# Sheet2.net
KiCad netlist of a schematic drawn in Altium Designer
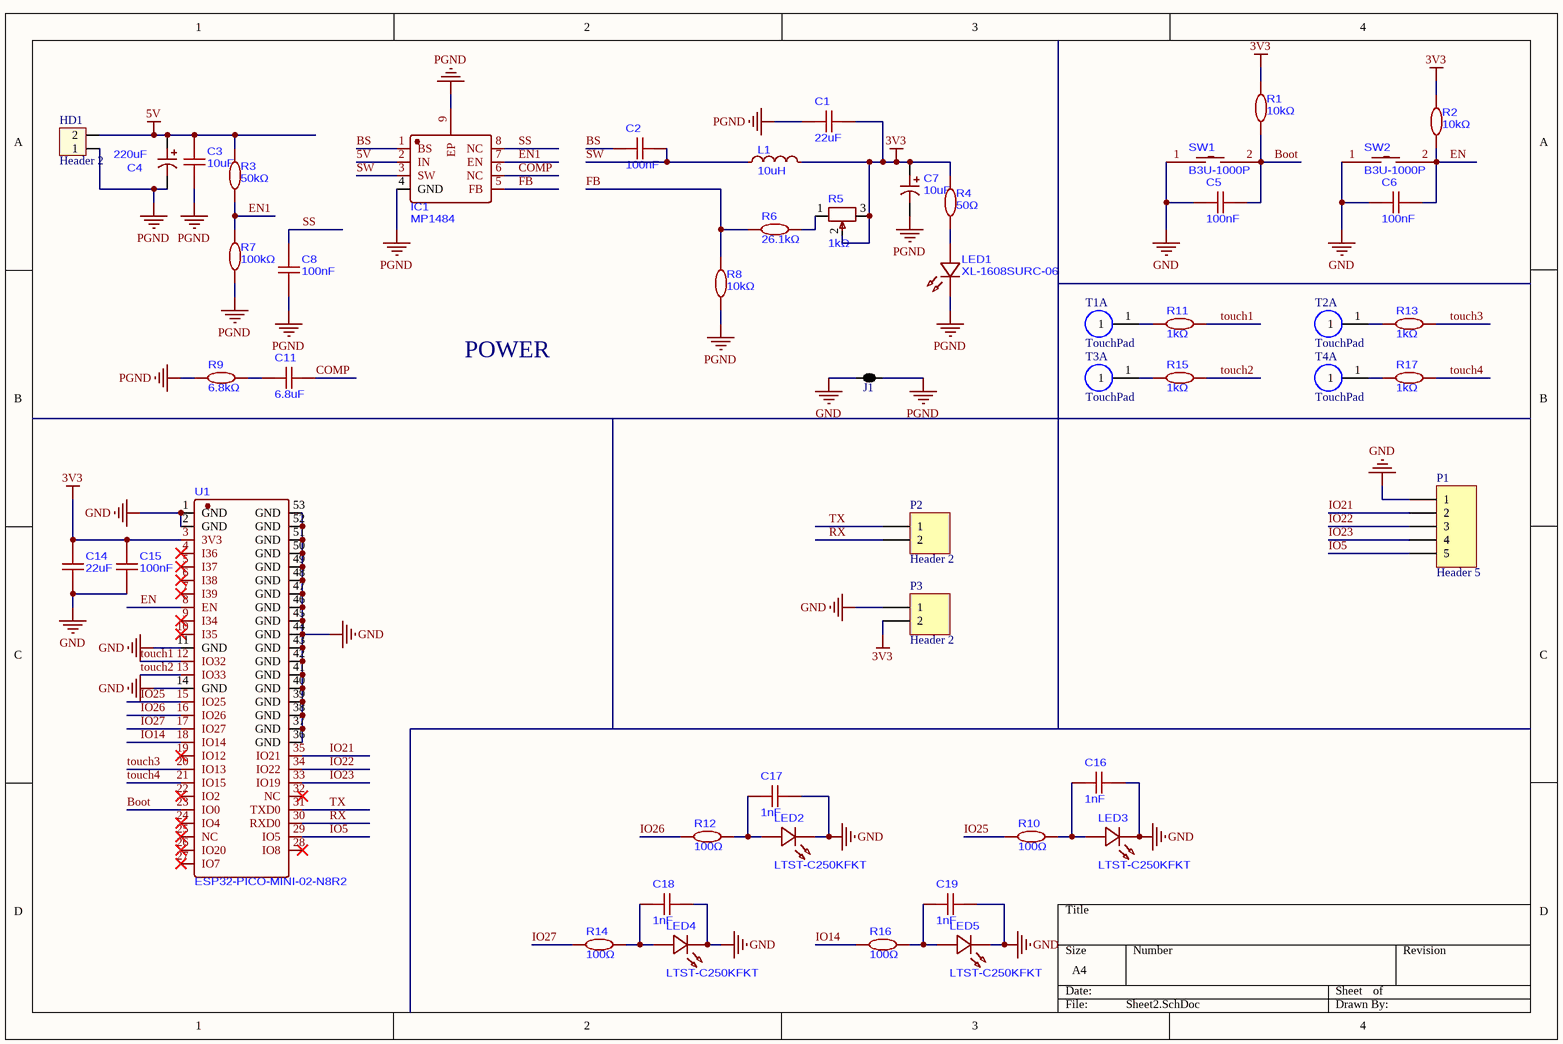
[diagram p0: Sheet2.SchDoc]

(export (version "E")
  (design (tool "Eeschema 10.0.6"))
  (components
    (comp (ref "C1")
      (value "22uF")
      (footprint "C0603")
      (description "10V 22uF X5R ±20% 0603 Ceramic Capacitors ROHS")
      (libsource (lib "Schlib2") (part "CL10A226MP8NUNE"))
    )
    (comp (ref "C2")
      (value "100nF")
      (footprint "C0603")
      (description "50V 100nF X7R ±10% 0603 Ceramic Capacitors ROHS")
      (libsource (lib "Schlib2") (part "CC0603KRX7R9BB104"))
    )
    (comp (ref "C3")
      (value "10uF")
      (footprint "C0603")
      (description "10V 10uF X5R ±10% 0603 Ceramic Capacitors ROHS")
      (libsource (lib "Schlib2") (part "CL10A106KP8NNNC"))
    )
    (comp (ref "C4")
      (value "220uF")
      (footprint "CAP-SMD_BD6.3-L6.6-W6.6-FD")
      (description "220uF 10V ±20% 69mA@120Hz SMD,D6.3xL5.4mm Aluminum Electrolytic Capacitors ROHS")
      (libsource (lib "Schlib2") (part "RVT220UF10V67RV0037"))
    )
    (comp (ref "C5")
      (value "100nF")
      (footprint "C0603")
      (description "50V 100nF X7R ±10% 0603 Ceramic Capacitors ROHS")
      (libsource (lib "Schlib2") (part "CC0603KRX7R9BB104"))
    )
    (comp (ref "C6")
      (value "100nF")
      (footprint "C0603")
      (description "50V 100nF X7R ±10% 0603 Ceramic Capacitors ROHS")
      (libsource (lib "Schlib2") (part "CC0603KRX7R9BB104"))
    )
    (comp (ref "C7")
      (value "10uF")
      (footprint "CAP-SMD_BD6.3-L6.6-W6.6-FD")
      (description "10uF 50V 24mA@120Hz ±20% SMD,D5xL5.4mm Aluminum Electrolytic Capacitors ROHS")
      (libsource (lib "Schlib2") (part "RST10UF50V016"))
    )
    (comp (ref "C8")
      (value "100nF")
      (footprint "C0603")
      (description "50V 100nF X7R ±10% 0603 Ceramic Capacitors ROHS")
      (libsource (lib "Schlib2") (part "CC0603KRX7R9BB104"))
    )
    (comp (ref "C11")
      (value "6.8uF")
      (footprint "C0603")
      (description "10V 6.8uF X5R ±10% 0603 Ceramic Capacitors ROHS")
      (libsource (lib "Schlib2") (part "C1608X5R1A685KT000E"))
    )
    (comp (ref "C14")
      (value "22uF")
      (footprint "C0603")
      (description "10V 22uF X5R ±20% 0603 Ceramic Capacitors ROHS")
      (libsource (lib "Schlib2") (part "CL10A226MP8NUNE"))
    )
    (comp (ref "C15")
      (value "100nF")
      (footprint "C0603")
      (description "50V 100nF X7R ±10% 0603 Ceramic Capacitors ROHS")
      (libsource (lib "Schlib2") (part "CC0603KRX7R9BB104"))
    )
    (comp (ref "C16")
      (value "1nF")
      (footprint "C0603")
      (description "50V 1nF X7R ±10% 0603 Ceramic Capacitors ROHS")
      (libsource (lib "Schlib2") (part "CL10B102KB8NNNC"))
    )
    (comp (ref "C17")
      (value "1nF")
      (footprint "C0603")
      (description "50V 1nF X7R ±10% 0603 Ceramic Capacitors ROHS")
      (libsource (lib "Schlib2") (part "CL10B102KB8NNNC"))
    )
    (comp (ref "C18")
      (value "1nF")
      (footprint "C0603")
      (description "50V 1nF X7R ±10% 0603 Ceramic Capacitors ROHS")
      (libsource (lib "Schlib2") (part "CL10B102KB8NNNC"))
    )
    (comp (ref "C19")
      (value "1nF")
      (footprint "C0603")
      (description "50V 1nF X7R ±10% 0603 Ceramic Capacitors ROHS")
      (libsource (lib "Schlib2") (part "CL10B102KB8NNNC"))
    )
    (comp (ref "HD1")
      (value "Header 2")
      (footprint "HED2")
      (description "Header 2 (Green)")
      (libsource (lib "Library AL") (part "Hed2"))
    )
    (comp (ref "IC1")
      (value "MP1484")
      (footprint "SOP-8_L4.9-W3.9-P1.27-LS6.0-BL-EP3.1")
      (description "The MP1484 is a monolithic synchronous buck \r\nregulator.")
      (libsource (lib "Schlib2") (part "MP1484"))
    )
    (comp (ref "J1")
      (value "2 way net tie junction")
      (footprint "2way_HP")
      (libsource (lib "NetTie") (part "2way"))
    )
    (comp (ref "L1")
      (value "10uH")
      (footprint "IND-SMD_L6.0-W6.0_VLS6045EX-2R0N")
      (description "3.4A 10uH ±20% 3.9A 47mΩ SMD,6x6mm Fixed Inductors ROHS")
      (libsource (lib "Schlib2") (part "VLS6045EX-100M"))
    )
    (comp (ref "LED1")
      (value "XL-1608SURC-06")
      (footprint "LED0603-RD_RED")
      (libsource (lib "Schlib2") (part "XL-1608SURC-06"))
    )
    (comp (ref "LED2")
      (value "LTST-C250KFKT")
      (footprint "LED1206_LTST-C230KRKT")
      (description "20mA Orange 1.6V~2.4V 62.5mW 1205 LED Indication - Discrete ROHS")
      (libsource (lib "Schlib2") (part "LTST-C250KFKT"))
    )
    (comp (ref "LED3")
      (value "LTST-C250KFKT")
      (footprint "LED1206_LTST-C230KRKT")
      (description "20mA Orange 1.6V~2.4V 62.5mW 1205 LED Indication - Discrete ROHS")
      (libsource (lib "Schlib2") (part "LTST-C250KFKT"))
    )
    (comp (ref "LED4")
      (value "LTST-C250KFKT")
      (footprint "LED1206_LTST-C230KRKT")
      (description "20mA Orange 1.6V~2.4V 62.5mW 1205 LED Indication - Discrete ROHS")
      (libsource (lib "Schlib2") (part "LTST-C250KFKT"))
    )
    (comp (ref "LED5")
      (value "LTST-C250KFKT")
      (footprint "LED1206_LTST-C230KRKT")
      (description "20mA Orange 1.6V~2.4V 62.5mW 1205 LED Indication - Discrete ROHS")
      (libsource (lib "Schlib2") (part "LTST-C250KFKT"))
    )
    (comp (ref "P1")
      (value "Header 5")
      (footprint "HDR1X5")
      (description "Header, 5-Pin")
      (fields (field (name "PUBLISHER") "Altium Limited"))
      (libsource (lib "Library AL") (part "Header 5"))
    )
    (comp (ref "P2")
      (value "Header 2")
      (footprint "HDR1X2")
      (description "Header, 2-Pin")
      (fields (field (name "PUBLISHER") "Altium Limited"))
      (libsource (lib "Library AL") (part "Header 2"))
    )
    (comp (ref "P3")
      (value "Header 2")
      (footprint "HDR1X2")
      (description "Header, 2-Pin")
      (fields (field (name "PUBLISHER") "Altium Limited"))
      (libsource (lib "Library AL") (part "Header 2"))
    )
    (comp (ref "R1")
      (value "10kΩ")
      (footprint "R0603")
      (description "100mW 10kΩ 75V ±100ppm/℃ Thick Film Resistor ±1% 0603 Chip Resistor - Surface Mount ROHS")
      (libsource (lib "Schlib2") (part "RC0603FR-0710KL"))
    )
    (comp (ref "R2")
      (value "10kΩ")
      (footprint "R0603")
      (description "100mW 10kΩ 75V ±100ppm/℃ Thick Film Resistor ±1% 0603 Chip Resistor - Surface Mount ROHS")
      (libsource (lib "Schlib2") (part "RC0603FR-0710KL"))
    )
    (comp (ref "R3")
      (value "50kΩ")
      (footprint "R0603")
      (description "50kΩ 100mW 75V ±25ppm/℃ Thin Film Resistor ±0.1% 0603 Chip Resistor - Surface Mount ROHS")
      (libsource (lib "Schlib2") (part "RT0603BRD0750KL"))
    )
    (comp (ref "R4")
      (value "50Ω")
      (footprint "R0603")
      (description "100mW 50Ω 75V ±50ppm/℃ Thin Film Resistor ±0.1% 0603 Chip Resistor - Surface Mount ROHS")
      (libsource (lib "Schlib2") (part "RT0603BRE0750RL"))
    )
    (comp (ref "R5")
      (value "1kΩ")
      (footprint "RES-ADJ-SMD_3P-L4.5-W4.5-P2.30-BL-FS")
      (description "±20% ±100ppm/℃ 250mW 1kΩ SMD,4.5x4.5mm Trimmer Potentiometers ROHS")
      (libsource (lib "Schlib2") (part "3314J-1-102E"))
    )
    (comp (ref "R6")
      (value "26.1kΩ")
      (footprint "R0603")
      (description "100mW 26.1kΩ 75V ±100ppm/℃ Thick Film Resistor ±1% 0603 Chip Resistor - Surface Mount ROHS")
      (libsource (lib "Schlib2") (part "0603WAF2612T5E"))
    )
    (comp (ref "R7")
      (value "100kΩ")
      (footprint "R0603")
      (description "100mW 100kΩ 75V ±100ppm/℃ Thick Film Resistor ±1% 0603 Chip Resistor - Surface Mount ROHS")
      (libsource (lib "Schlib2") (part "RC0603FR-07100KL"))
    )
    (comp (ref "R8")
      (value "10kΩ")
      (footprint "R0603")
      (description "100mW 10kΩ 75V ±100ppm/℃ Thick Film Resistor ±1% 0603 Chip Resistor - Surface Mount ROHS")
      (libsource (lib "Schlib2") (part "RC0603FR-0710KL"))
    )
    (comp (ref "R9")
      (value "6.8kΩ")
      (footprint "R0603")
      (description "6.8kΩ 100mW 75V ±100ppm/℃ Thick Film Resistor ±1% 0603 Chip Resistor - Surface Mount ROHS")
      (libsource (lib "Schlib2") (part "FRC0603F6801TS"))
    )
    (comp (ref "R10")
      (value "100Ω")
      (footprint "R0603")
      (description "100mW 100Ω 75V ±100ppm/℃ Thick Film Resistor ±1% 0603 Chip Resistor - Surface Mount ROHS")
      (libsource (lib "Schlib2") (part "RC0603FR-07100RL"))
    )
    (comp (ref "R11")
      (value "1kΩ")
      (footprint "R0603")
      (description "100mW 1kΩ 50V ±100ppm/℃ Thick Film Resistor ±5% 0603 Chip Resistor - Surface Mount ROHS")
      (libsource (lib "Schlib2") (part "RMC 0603 1K J N"))
    )
    (comp (ref "R12")
      (value "100Ω")
      (footprint "R0603")
      (description "100mW 100Ω 75V ±100ppm/℃ Thick Film Resistor ±1% 0603 Chip Resistor - Surface Mount ROHS")
      (libsource (lib "Schlib2") (part "RC0603FR-07100RL"))
    )
    (comp (ref "R13")
      (value "1kΩ")
      (footprint "R0603")
      (description "100mW 1kΩ 50V ±100ppm/℃ Thick Film Resistor ±5% 0603 Chip Resistor - Surface Mount ROHS")
      (libsource (lib "Schlib2") (part "RMC 0603 1K J N"))
    )
    (comp (ref "R14")
      (value "100Ω")
      (footprint "R0603")
      (description "100mW 100Ω 75V ±100ppm/℃ Thick Film Resistor ±1% 0603 Chip Resistor - Surface Mount ROHS")
      (libsource (lib "Schlib2") (part "RC0603FR-07100RL"))
    )
    (comp (ref "R15")
      (value "1kΩ")
      (footprint "R0603")
      (description "100mW 1kΩ 50V ±100ppm/℃ Thick Film Resistor ±5% 0603 Chip Resistor - Surface Mount ROHS")
      (libsource (lib "Schlib2") (part "RMC 0603 1K J N"))
    )
    (comp (ref "R16")
      (value "100Ω")
      (footprint "R0603")
      (description "100mW 100Ω 75V ±100ppm/℃ Thick Film Resistor ±1% 0603 Chip Resistor - Surface Mount ROHS")
      (libsource (lib "Schlib2") (part "RC0603FR-07100RL"))
    )
    (comp (ref "R17")
      (value "1kΩ")
      (footprint "R0603")
      (description "100mW 1kΩ 50V ±100ppm/℃ Thick Film Resistor ±5% 0603 Chip Resistor - Surface Mount ROHS")
      (libsource (lib "Schlib2") (part "RMC 0603 1K J N"))
    )
    (comp (ref "SW1")
      (value "B3U-1000P")
      (footprint "KEY-SMD_B3U-1000PM")
      (description "12V 2.5mm Round Button 3mm SPST 50mA SMD,3x2.5mm Tactile Switches ROHS")
      (libsource (lib "Schlib2") (part "B3U-1000P"))
    )
    (comp (ref "SW2")
      (value "B3U-1000P")
      (footprint "KEY-SMD_B3U-1000PM")
      (description "12V 2.5mm Round Button 3mm SPST 50mA SMD,3x2.5mm Tactile Switches ROHS")
      (libsource (lib "Schlib2") (part "B3U-1000P"))
    )
    (comp (ref "T1")
      (value "TouchPad")
      (footprint "TouchPad")
      (description "pad cam ung dien dung")
      (libsource (lib "Schlib2") (part "TouchPad"))
    )
    (comp (ref "T2")
      (value "TouchPad")
      (footprint "TouchPad")
      (description "pad cam ung dien dung")
      (libsource (lib "Schlib2") (part "TouchPad"))
    )
    (comp (ref "T3")
      (value "TouchPad")
      (footprint "TouchPad")
      (description "pad cam ung dien dung")
      (libsource (lib "Schlib2") (part "TouchPad"))
    )
    (comp (ref "T4")
      (value "TouchPad")
      (footprint "TouchPad")
      (description "pad cam ung dien dung")
      (libsource (lib "Schlib2") (part "TouchPad"))
    )
    (comp (ref "U1")
      (value "ESP32-PICO-MINI-02-N8R2")
      (footprint "BULETM-SMD_ESP32-PICO-MINI-02-N8R2")
      (libsource (lib "Schlib2") (part "ESP32-PICO-MINI-02-N8R2"))
    )
  )
  (nets
    (net (code "1") (name "/BS") (class "Default")
      (node (ref "C2") (pin "2") (pinfunction "2_2") (pintype "passive"))
      (node (ref "IC1") (pin "1") (pinfunction "BS_1") (pintype "passive"))
    )
    (net (code "2") (name "/Boot") (class "Default")
      (node (ref "C5") (pin "1") (pinfunction "1_1") (pintype "passive"))
      (node (ref "R1") (pin "1") (pinfunction "1_1") (pintype "passive"))
      (node (ref "SW1") (pin "2") (pinfunction "2_2") (pintype "passive"))
      (node (ref "U1") (pin "23") (pinfunction "IO0_23") (pintype "passive"))
    )
    (net (code "3") (name "/COMP") (class "Default")
      (node (ref "C11") (pin "2") (pinfunction "2_2") (pintype "passive"))
      (node (ref "IC1") (pin "6") (pinfunction "NC_6") (pintype "passive"))
    )
    (net (code "4") (name "/EN") (class "Default")
      (node (ref "C6") (pin "1") (pinfunction "1_1") (pintype "passive"))
      (node (ref "R2") (pin "1") (pinfunction "1_1") (pintype "passive"))
      (node (ref "SW2") (pin "2") (pinfunction "2_2") (pintype "passive"))
      (node (ref "U1") (pin "8") (pinfunction "EN_8") (pintype "passive"))
    )
    (net (code "5") (name "/EN1") (class "Default")
      (node (ref "IC1") (pin "7") (pinfunction "EN_7") (pintype "passive"))
      (node (ref "R3") (pin "1") (pinfunction "1_1") (pintype "passive"))
      (node (ref "R7") (pin "2") (pinfunction "2_2") (pintype "passive"))
    )
    (net (code "6") (name "/FB") (class "Default")
      (node (ref "IC1") (pin "5") (pinfunction "FB_5") (pintype "passive"))
      (node (ref "R6") (pin "1") (pinfunction "1_1") (pintype "passive"))
      (node (ref "R8") (pin "2") (pinfunction "2_2") (pintype "passive"))
    )
    (net (code "7") (name "/IO5") (class "Default")
      (node (ref "P1") (pin "5") (pinfunction "5_5") (pintype "passive"))
      (node (ref "U1") (pin "29") (pinfunction "IO5_29") (pintype "passive"))
    )
    (net (code "8") (name "/IO14") (class "Default")
      (node (ref "R16") (pin "1") (pinfunction "1_1") (pintype "passive"))
      (node (ref "U1") (pin "18") (pinfunction "IO14_18") (pintype "passive"))
    )
    (net (code "9") (name "/IO21") (class "Default")
      (node (ref "P1") (pin "2") (pinfunction "2_2") (pintype "passive"))
      (node (ref "U1") (pin "35") (pinfunction "IO21_35") (pintype "passive"))
    )
    (net (code "10") (name "/IO22") (class "Default")
      (node (ref "P1") (pin "3") (pinfunction "3_3") (pintype "passive"))
      (node (ref "U1") (pin "34") (pinfunction "IO22_34") (pintype "passive"))
    )
    (net (code "11") (name "/IO23") (class "Default")
      (node (ref "P1") (pin "4") (pinfunction "4_4") (pintype "passive"))
      (node (ref "U1") (pin "33") (pinfunction "IO19_33") (pintype "passive"))
    )
    (net (code "12") (name "/IO25") (class "Default")
      (node (ref "R10") (pin "1") (pinfunction "1_1") (pintype "passive"))
      (node (ref "U1") (pin "15") (pinfunction "IO25_15") (pintype "passive"))
    )
    (net (code "13") (name "/IO26") (class "Default")
      (node (ref "R12") (pin "1") (pinfunction "1_1") (pintype "passive"))
      (node (ref "U1") (pin "16") (pinfunction "IO26_16") (pintype "passive"))
    )
    (net (code "14") (name "/IO27") (class "Default")
      (node (ref "R14") (pin "1") (pinfunction "1_1") (pintype "passive"))
      (node (ref "U1") (pin "17") (pinfunction "IO27_17") (pintype "passive"))
    )
    (net (code "15") (name "/RX") (class "Default")
      (node (ref "P2") (pin "2") (pinfunction "2_2") (pintype "passive"))
      (node (ref "U1") (pin "30") (pinfunction "RXD0_30") (pintype "passive"))
    )
    (net (code "16") (name "/SS") (class "Default")
      (node (ref "C8") (pin "2") (pinfunction "2_2") (pintype "passive"))
      (node (ref "IC1") (pin "8") (pinfunction "NC_8") (pintype "passive"))
    )
    (net (code "17") (name "/SW") (class "Default")
      (node (ref "C2") (pin "1") (pinfunction "1_1") (pintype "passive"))
      (node (ref "IC1") (pin "3") (pinfunction "SW_3") (pintype "passive"))
      (node (ref "L1") (pin "1") (pinfunction "1_1") (pintype "passive"))
    )
    (net (code "18") (name "/TX") (class "Default")
      (node (ref "P2") (pin "1") (pinfunction "1_1") (pintype "passive"))
      (node (ref "U1") (pin "31") (pinfunction "TXD0_31") (pintype "passive"))
    )
    (net (code "19") (name "/touch1") (class "Default")
      (node (ref "R11") (pin "2") (pinfunction "2_2") (pintype "passive"))
      (node (ref "U1") (pin "12") (pinfunction "IO32_12") (pintype "passive"))
    )
    (net (code "20") (name "/touch2") (class "Default")
      (node (ref "R15") (pin "2") (pinfunction "2_2") (pintype "passive"))
      (node (ref "U1") (pin "13") (pinfunction "IO33_13") (pintype "passive"))
    )
    (net (code "21") (name "/touch3") (class "Default")
      (node (ref "R13") (pin "2") (pinfunction "2_2") (pintype "passive"))
      (node (ref "U1") (pin "20") (pinfunction "IO13_20") (pintype "passive"))
    )
    (net (code "22") (name "/touch4") (class "Default")
      (node (ref "R17") (pin "2") (pinfunction "2_2") (pintype "passive"))
      (node (ref "U1") (pin "21") (pinfunction "IO15_21") (pintype "passive"))
    )
    (net (code "23") (name "3V3") (class "Default")
      (node (ref "C1") (pin "2") (pinfunction "2_2") (pintype "passive"))
      (node (ref "C14") (pin "2") (pinfunction "2_2") (pintype "passive"))
      (node (ref "C15") (pin "1") (pinfunction "1_1") (pintype "passive"))
      (node (ref "C7") (pin "1") (pinfunction "1_1") (pintype "passive"))
      (node (ref "L1") (pin "2") (pinfunction "2_2") (pintype "passive"))
      (node (ref "P3") (pin "2") (pinfunction "2_2") (pintype "passive"))
      (node (ref "R1") (pin "2") (pinfunction "2_2") (pintype "passive"))
      (node (ref "R2") (pin "2") (pinfunction "2_2") (pintype "passive"))
      (node (ref "R4") (pin "2") (pinfunction "2_2") (pintype "passive"))
      (node (ref "R5") (pin "2") (pinfunction "2_2") (pintype "passive"))
      (node (ref "R5") (pin "3") (pinfunction "3_3") (pintype "passive"))
      (node (ref "U1") (pin "3") (pinfunction "3V3_3") (pintype "passive"))
    )
    (net (code "24") (name "5V") (class "Default")
      (node (ref "C3") (pin "2") (pinfunction "2_2") (pintype "passive"))
      (node (ref "C4") (pin "1") (pinfunction "1_1") (pintype "passive"))
      (node (ref "HD1") (pin "2") (pinfunction "2_2") (pintype "passive"))
      (node (ref "IC1") (pin "2") (pinfunction "IN_2") (pintype "passive"))
      (node (ref "R3") (pin "2") (pinfunction "2_2") (pintype "passive"))
    )
    (net (code "25") (name "GND") (class "Default")
      (node (ref "C14") (pin "1") (pinfunction "1_1") (pintype "passive"))
      (node (ref "C15") (pin "2") (pinfunction "2_2") (pintype "passive"))
      (node (ref "C16") (pin "2") (pinfunction "2_2") (pintype "passive"))
      (node (ref "C17") (pin "2") (pinfunction "2_2") (pintype "passive"))
      (node (ref "C18") (pin "2") (pinfunction "2_2") (pintype "passive"))
      (node (ref "C19") (pin "2") (pinfunction "2_2") (pintype "passive"))
      (node (ref "C5") (pin "2") (pinfunction "2_2") (pintype "passive"))
      (node (ref "C6") (pin "2") (pinfunction "2_2") (pintype "passive"))
      (node (ref "J1") (pin "1") (pinfunction "1_1") (pintype "passive"))
      (node (ref "LED2") (pin "2") (pinfunction "C_2") (pintype "passive"))
      (node (ref "LED3") (pin "2") (pinfunction "C_2") (pintype "passive"))
      (node (ref "LED4") (pin "2") (pinfunction "C_2") (pintype "passive"))
      (node (ref "LED5") (pin "2") (pinfunction "C_2") (pintype "passive"))
      (node (ref "P1") (pin "1") (pinfunction "1_1") (pintype "passive"))
      (node (ref "P3") (pin "1") (pinfunction "1_1") (pintype "passive"))
      (node (ref "SW1") (pin "1") (pinfunction "1_1") (pintype "passive"))
      (node (ref "SW2") (pin "1") (pinfunction "1_1") (pintype "passive"))
      (node (ref "U1") (pin "1") (pinfunction "GND_1") (pintype "passive"))
      (node (ref "U1") (pin "11") (pinfunction "GND_11") (pintype "passive"))
      (node (ref "U1") (pin "14") (pinfunction "GND_14") (pintype "passive"))
      (node (ref "U1") (pin "2") (pinfunction "GND_2") (pintype "passive"))
      (node (ref "U1") (pin "36") (pinfunction "GND_36") (pintype "passive"))
      (node (ref "U1") (pin "37") (pinfunction "GND_37") (pintype "passive"))
      (node (ref "U1") (pin "38") (pinfunction "GND_38") (pintype "passive"))
      (node (ref "U1") (pin "39") (pinfunction "GND_39") (pintype "passive"))
      (node (ref "U1") (pin "40") (pinfunction "GND_40") (pintype "passive"))
      (node (ref "U1") (pin "41") (pinfunction "GND_41") (pintype "passive"))
      (node (ref "U1") (pin "42") (pinfunction "GND_42") (pintype "passive"))
      (node (ref "U1") (pin "43") (pinfunction "GND_43") (pintype "passive"))
      (node (ref "U1") (pin "44") (pinfunction "GND_44") (pintype "passive"))
      (node (ref "U1") (pin "45") (pinfunction "GND_45") (pintype "passive"))
      (node (ref "U1") (pin "46") (pinfunction "GND_46") (pintype "passive"))
      (node (ref "U1") (pin "47") (pinfunction "GND_47") (pintype "passive"))
      (node (ref "U1") (pin "48") (pinfunction "GND_48") (pintype "passive"))
      (node (ref "U1") (pin "49") (pinfunction "GND_49") (pintype "passive"))
      (node (ref "U1") (pin "50") (pinfunction "GND_50") (pintype "passive"))
      (node (ref "U1") (pin "51") (pinfunction "GND_51") (pintype "passive"))
      (node (ref "U1") (pin "52") (pinfunction "GND_52") (pintype "passive"))
      (node (ref "U1") (pin "53") (pinfunction "GND_53") (pintype "passive"))
    )
    (net (code "26") (name "Net-(C11-Pad1)") (class "Default")
      (node (ref "C11") (pin "1") (pinfunction "1_1") (pintype "passive"))
      (node (ref "R9") (pin "2") (pinfunction "2_2") (pintype "passive"))
    )
    (net (code "27") (name "Net-(LED1-A)") (class "Default")
      (node (ref "LED1") (pin "2") (pinfunction "A_2") (pintype "passive"))
      (node (ref "R4") (pin "1") (pinfunction "1_1") (pintype "passive"))
    )
    (net (code "28") (name "Net-(LED2-A)") (class "Default")
      (node (ref "C17") (pin "1") (pinfunction "1_1") (pintype "passive"))
      (node (ref "LED2") (pin "1") (pinfunction "A_1") (pintype "passive"))
      (node (ref "R12") (pin "2") (pinfunction "2_2") (pintype "passive"))
    )
    (net (code "29") (name "Net-(LED3-A)") (class "Default")
      (node (ref "C16") (pin "1") (pinfunction "1_1") (pintype "passive"))
      (node (ref "LED3") (pin "1") (pinfunction "A_1") (pintype "passive"))
      (node (ref "R10") (pin "2") (pinfunction "2_2") (pintype "passive"))
    )
    (net (code "30") (name "Net-(LED4-A)") (class "Default")
      (node (ref "C18") (pin "1") (pinfunction "1_1") (pintype "passive"))
      (node (ref "LED4") (pin "1") (pinfunction "A_1") (pintype "passive"))
      (node (ref "R14") (pin "2") (pinfunction "2_2") (pintype "passive"))
    )
    (net (code "31") (name "Net-(LED5-A)") (class "Default")
      (node (ref "C19") (pin "1") (pinfunction "1_1") (pintype "passive"))
      (node (ref "LED5") (pin "1") (pinfunction "A_1") (pintype "passive"))
      (node (ref "R16") (pin "2") (pinfunction "2_2") (pintype "passive"))
    )
    (net (code "32") (name "Net-(R5-Pad1)") (class "Default")
      (node (ref "R5") (pin "1") (pinfunction "1_1") (pintype "passive"))
      (node (ref "R6") (pin "2") (pinfunction "2_2") (pintype "passive"))
    )
    (net (code "33") (name "Net-(R11-Pad1)") (class "Default")
      (node (ref "R11") (pin "1") (pinfunction "1_1") (pintype "passive"))
      (node (ref "T1") (pin "1") (pinfunction "1_1") (pintype "passive"))
    )
    (net (code "34") (name "Net-(R13-Pad1)") (class "Default")
      (node (ref "R13") (pin "1") (pinfunction "1_1") (pintype "passive"))
      (node (ref "T2") (pin "1") (pinfunction "1_1") (pintype "passive"))
    )
    (net (code "35") (name "Net-(R15-Pad1)") (class "Default")
      (node (ref "R15") (pin "1") (pinfunction "1_1") (pintype "passive"))
      (node (ref "T3") (pin "1") (pinfunction "1_1") (pintype "passive"))
    )
    (net (code "36") (name "Net-(R17-Pad1)") (class "Default")
      (node (ref "R17") (pin "1") (pinfunction "1_1") (pintype "passive"))
      (node (ref "T4") (pin "1") (pinfunction "1_1") (pintype "passive"))
    )
    (net (code "37") (name "PGND") (class "Default")
      (node (ref "C1") (pin "1") (pinfunction "1_1") (pintype "passive"))
      (node (ref "C3") (pin "1") (pinfunction "1_1") (pintype "passive"))
      (node (ref "C4") (pin "2") (pinfunction "2_2") (pintype "passive"))
      (node (ref "C7") (pin "2") (pinfunction "2_2") (pintype "passive"))
      (node (ref "C8") (pin "1") (pinfunction "1_1") (pintype "passive"))
      (node (ref "HD1") (pin "1") (pinfunction "1_1") (pintype "passive"))
      (node (ref "IC1") (pin "4") (pinfunction "GND_4") (pintype "passive"))
      (node (ref "IC1") (pin "9") (pinfunction "EP_9") (pintype "passive"))
      (node (ref "J1") (pin "2") (pinfunction "2_2") (pintype "passive"))
      (node (ref "LED1") (pin "1") (pinfunction "K_1") (pintype "passive"))
      (node (ref "R7") (pin "1") (pinfunction "1_1") (pintype "passive"))
      (node (ref "R8") (pin "1") (pinfunction "1_1") (pintype "passive"))
      (node (ref "R9") (pin "1") (pinfunction "1_1") (pintype "passive"))
    )
    (net (code "38") (name "unconnected-(U1-I34-Pad9)") (class "Default")
      (node (ref "U1") (pin "9") (pinfunction "I34_9") (pintype "passive+no_connect"))
    )
    (net (code "39") (name "unconnected-(U1-I35-Pad10)") (class "Default")
      (node (ref "U1") (pin "10") (pinfunction "I35_10") (pintype "passive+no_connect"))
    )
    (net (code "40") (name "unconnected-(U1-I36-Pad4)") (class "Default")
      (node (ref "U1") (pin "4") (pinfunction "I36_4") (pintype "passive+no_connect"))
    )
    (net (code "41") (name "unconnected-(U1-I37-Pad5)") (class "Default")
      (node (ref "U1") (pin "5") (pinfunction "I37_5") (pintype "passive+no_connect"))
    )
    (net (code "42") (name "unconnected-(U1-I38-Pad6)") (class "Default")
      (node (ref "U1") (pin "6") (pinfunction "I38_6") (pintype "passive+no_connect"))
    )
    (net (code "43") (name "unconnected-(U1-I39-Pad7)") (class "Default")
      (node (ref "U1") (pin "7") (pinfunction "I39_7") (pintype "passive+no_connect"))
    )
    (net (code "44") (name "unconnected-(U1-IO2-Pad22)") (class "Default")
      (node (ref "U1") (pin "22") (pinfunction "IO2_22") (pintype "passive+no_connect"))
    )
    (net (code "45") (name "unconnected-(U1-IO4-Pad24)") (class "Default")
      (node (ref "U1") (pin "24") (pinfunction "IO4_24") (pintype "passive+no_connect"))
    )
    (net (code "46") (name "unconnected-(U1-IO7-Pad27)") (class "Default")
      (node (ref "U1") (pin "27") (pinfunction "IO7_27") (pintype "passive+no_connect"))
    )
    (net (code "47") (name "unconnected-(U1-IO8-Pad28)") (class "Default")
      (node (ref "U1") (pin "28") (pinfunction "IO8_28") (pintype "passive+no_connect"))
    )
    (net (code "48") (name "unconnected-(U1-IO12-Pad19)") (class "Default")
      (node (ref "U1") (pin "19") (pinfunction "IO12_19") (pintype "passive+no_connect"))
    )
    (net (code "49") (name "unconnected-(U1-IO20-Pad26)") (class "Default")
      (node (ref "U1") (pin "26") (pinfunction "IO20_26") (pintype "passive+no_connect"))
    )
    (net (code "50") (name "unconnected-(U1-NC-Pad25)") (class "Default")
      (node (ref "U1") (pin "25") (pinfunction "NC_25") (pintype "passive+no_connect"))
    )
    (net (code "51") (name "unconnected-(U1-NC-Pad32)") (class "Default")
      (node (ref "U1") (pin "32") (pinfunction "NC_32") (pintype "passive+no_connect"))
    )
  )
)
